# rs485.net
KiCad netlist of a schematic drawn in Altium Designer
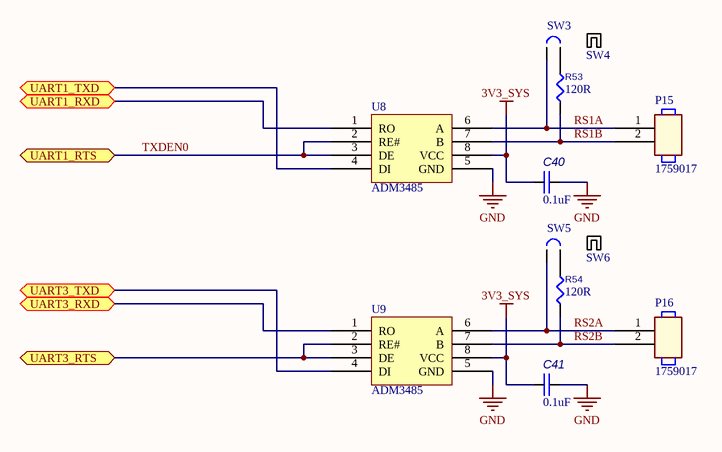
[diagram p0: rs485.SchDoc]

(export (version "E")
  (design (tool "Eeschema 10.0.6"))
  (components
    (comp (ref "C40")
      (value "0.1uF")
      (footprint "CC1608-0603")
      (description "C0603")
      (libsource (lib "spider") (part "C0603"))
    )
    (comp (ref "C41")
      (value "0.1uF")
      (footprint "CC1608-0603")
      (description "C0603")
      (libsource (lib "spider") (part "C0603"))
    )
    (comp (ref "P15")
      (value "TE_282814-2")
      (footprint "TE_282814-2")
      (description "Terminal Block Connectors")
      (fields (field (name "MANUFACTURER") "TE Connectivity") (field (name "P/N2") "1759017"))
      (libsource (lib "spider") (part "TE_282814-2"))
    )
    (comp (ref "P16")
      (value "TE_282814-2")
      (footprint "TE_282814-2")
      (description "Terminal Block Connectors")
      (fields (field (name "MANUFACTURER") "TE Connectivity") (field (name "P/N2") "1759017"))
      (libsource (lib "spider") (part "TE_282814-2"))
    )
    (comp (ref "R53")
      (value "120R")
      (footprint "RESC1608X55N")
      (description "R0603")
      (libsource (lib "pmvent") (part "R0603"))
    )
    (comp (ref "R54")
      (value "120R")
      (footprint "RESC1608X55N")
      (description "R0603")
      (libsource (lib "pmvent") (part "R0603"))
    )
    (comp (ref "SW3")
      (value "Jumper 2-pin")
      (footprint "JUMPER_2")
      (description "Jumper 2-pin 2.54mm")
      (libsource (lib "pmvent") (part "Jumper 2-pin"))
    )
    (comp (ref "SW4")
      (value "Jumper")
      (description "Jumper 2.54mm")
      (libsource (lib "pmvent") (part "Jumper"))
    )
    (comp (ref "SW5")
      (value "Jumper 2-pin")
      (footprint "JUMPER_2")
      (description "Jumper 2-pin 2.54mm")
      (libsource (lib "pmvent") (part "Jumper 2-pin"))
    )
    (comp (ref "SW6")
      (value "Jumper")
      (description "Jumper 2.54mm")
      (libsource (lib "pmvent") (part "Jumper"))
    )
    (comp (ref "U8")
      (value "ADM3485")
      (footprint "SOIC127P600X175-8N")
      (description "RS-485 Half-Duplex transceiver")
      (libsource (lib "pmvent") (part "ADM3485"))
    )
    (comp (ref "U9")
      (value "ADM3485")
      (footprint "SOIC127P600X175-8N")
      (description "RS-485 Half-Duplex transceiver")
      (libsource (lib "pmvent") (part "ADM3485"))
    )
  )
  (nets
    (net (code "1") (name "/RS1A") (class "Default")
      (node (ref "P15") (pin "1") (pinfunction "1_1") (pintype "passive"))
      (node (ref "SW3") (pin "1") (pinfunction "1_1") (pintype "passive"))
      (node (ref "U8") (pin "6") (pinfunction "A_6") (pintype "passive"))
    )
    (net (code "2") (name "/RS1B") (class "Default")
      (node (ref "P15") (pin "2") (pinfunction "2_2") (pintype "passive"))
      (node (ref "R53") (pin "1") (pinfunction "1_1") (pintype "passive"))
      (node (ref "U8") (pin "7") (pinfunction "B_7") (pintype "passive"))
    )
    (net (code "3") (name "/RS2A") (class "Default")
      (node (ref "P16") (pin "1") (pinfunction "1_1") (pintype "passive"))
      (node (ref "SW5") (pin "1") (pinfunction "1_1") (pintype "passive"))
      (node (ref "U9") (pin "6") (pinfunction "A_6") (pintype "passive"))
    )
    (net (code "4") (name "/RS2B") (class "Default")
      (node (ref "P16") (pin "2") (pinfunction "2_2") (pintype "passive"))
      (node (ref "R54") (pin "1") (pinfunction "1_1") (pintype "passive"))
      (node (ref "U9") (pin "7") (pinfunction "B_7") (pintype "passive"))
    )
    (net (code "5") (name "/TXDEN0") (class "Default")
      (node (ref "U8") (pin "2") (pinfunction "RE#_2") (pintype "passive"))
      (node (ref "U8") (pin "3") (pinfunction "DE_3") (pintype "passive"))
    )
    (net (code "6") (name "/UART1_RXD") (class "Default")
      (node (ref "U8") (pin "1") (pinfunction "RO_1") (pintype "passive"))
    )
    (net (code "7") (name "/UART1_TXD") (class "Default")
      (node (ref "U8") (pin "4") (pinfunction "DI_4") (pintype "passive"))
    )
    (net (code "8") (name "/UART3_RTS") (class "Default")
      (node (ref "U9") (pin "2") (pinfunction "RE#_2") (pintype "passive"))
      (node (ref "U9") (pin "3") (pinfunction "DE_3") (pintype "passive"))
    )
    (net (code "9") (name "/UART3_RXD") (class "Default")
      (node (ref "U9") (pin "1") (pinfunction "RO_1") (pintype "passive"))
    )
    (net (code "10") (name "/UART3_TXD") (class "Default")
      (node (ref "U9") (pin "4") (pinfunction "DI_4") (pintype "passive"))
    )
    (net (code "11") (name "3V3_SYS") (class "Default")
      (node (ref "C40") (pin "1") (pinfunction "1_1") (pintype "passive"))
      (node (ref "C41") (pin "1") (pinfunction "1_1") (pintype "passive"))
      (node (ref "U8") (pin "8") (pinfunction "VCC_8") (pintype "passive"))
      (node (ref "U9") (pin "8") (pinfunction "VCC_8") (pintype "passive"))
    )
    (net (code "12") (name "GND") (class "Default")
      (node (ref "C40") (pin "2") (pinfunction "2_2") (pintype "passive"))
      (node (ref "C41") (pin "2") (pinfunction "2_2") (pintype "passive"))
      (node (ref "U8") (pin "5") (pinfunction "GND_5") (pintype "passive"))
      (node (ref "U9") (pin "5") (pinfunction "GND_5") (pintype "passive"))
    )
    (net (code "13") (name "Net-(R53-Pad2)") (class "Default")
      (node (ref "R53") (pin "2") (pinfunction "2_2") (pintype "passive"))
      (node (ref "SW3") (pin "2") (pinfunction "2_2") (pintype "passive"))
    )
    (net (code "14") (name "Net-(R54-Pad2)") (class "Default")
      (node (ref "R54") (pin "2") (pinfunction "2_2") (pintype "passive"))
      (node (ref "SW5") (pin "2") (pinfunction "2_2") (pintype "passive"))
    )
    (net (code "15") (name "unconnected-(SW4-Pad1)") (class "Default")
      (node (ref "SW4") (pin "1") (pinfunction "1_1") (pintype "passive"))
    )
    (net (code "16") (name "unconnected-(SW4-Pad2)") (class "Default")
      (node (ref "SW4") (pin "2") (pinfunction "2_2") (pintype "passive"))
    )
    (net (code "17") (name "unconnected-(SW6-Pad1)") (class "Default")
      (node (ref "SW6") (pin "1") (pinfunction "1_1") (pintype "passive"))
    )
    (net (code "18") (name "unconnected-(SW6-Pad2)") (class "Default")
      (node (ref "SW6") (pin "2") (pinfunction "2_2") (pintype "passive"))
    )
  )
)
